# MotorDriver.net
KiCad netlist of a schematic drawn in Altium Designer
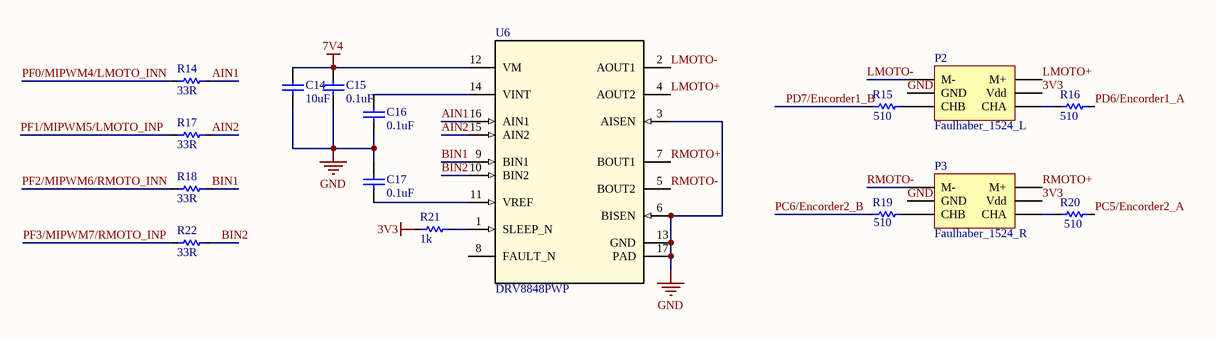
[diagram p0: MotorDriver.SchDoc]

(export (version "E")
  (design (tool "Eeschema 10.0.6"))
  (components
    (comp (ref "C14")
      (value "10uF")
      (footprint "1206")
      (description "Capacitor")
      (fields (field (name "Comment") "1uF/0603/50V") (field (name "PUBLISHER") "Altium Limited"))
      (libsource (lib "OurSuperMiniCar") (part "Cap"))
    )
    (comp (ref "C15")
      (value "0.1uF")
      (footprint "0603C")
      (description "Capacitor")
      (fields (field (name "Comment") "1uF/0603/50V") (field (name "PUBLISHER") "Altium Limited"))
      (libsource (lib "OurSuperMiniCar") (part "Cap"))
    )
    (comp (ref "C16")
      (value "0.1uF")
      (footprint "0603C")
      (description "Capacitor")
      (fields (field (name "Comment") "1uF/0603/50V") (field (name "PUBLISHER") "Altium Limited"))
      (libsource (lib "OurSuperMiniCar") (part "Cap"))
    )
    (comp (ref "C17")
      (value "0.1uF")
      (footprint "0603C")
      (description "Capacitor")
      (fields (field (name "Comment") "1uF/0603/50V") (field (name "PUBLISHER") "Altium Limited"))
      (libsource (lib "OurSuperMiniCar") (part "Cap"))
    )
    (comp (ref "P2")
      (value "Faulhaber_1524_L")
      (footprint "HDR2X3_2.0Mm")
      (libsource (lib "OurSuperMiniCar") (part "Faulhaber_1524"))
    )
    (comp (ref "P3")
      (value "Faulhaber_1524_R")
      (footprint "HDR2X3_2.0Mm")
      (libsource (lib "OurSuperMiniCar") (part "Faulhaber_1524"))
    )
    (comp (ref "R14")
      (value "33R")
      (footprint "0603R")
      (description "Resistor")
      (fields (field (name "PUBLISHER") "Altium Limited"))
      (libsource (lib "OurSuperMiniCar") (part "Res1"))
    )
    (comp (ref "R15")
      (value "510")
      (footprint "0603R")
      (description "Resistor")
      (fields (field (name "Comment") "1K/5%") (field (name "PUBLISHER") "Altium Limited"))
      (libsource (lib "MyComoonents") (part "Res1"))
    )
    (comp (ref "R16")
      (value "510")
      (footprint "0603R")
      (description "Resistor")
      (fields (field (name "PUBLISHER") "Altium Limited"))
      (libsource (lib "MyComoonents") (part "Res1"))
    )
    (comp (ref "R17")
      (value "33R")
      (footprint "0603R")
      (description "Resistor")
      (fields (field (name "PUBLISHER") "Altium Limited"))
      (libsource (lib "OurSuperMiniCar") (part "Res1"))
    )
    (comp (ref "R18")
      (value "33R")
      (footprint "0603R")
      (description "Resistor")
      (fields (field (name "PUBLISHER") "Altium Limited"))
      (libsource (lib "OurSuperMiniCar") (part "Res1"))
    )
    (comp (ref "R19")
      (value "510")
      (footprint "0603R")
      (description "Resistor")
      (fields (field (name "Comment") "1K/5%") (field (name "PUBLISHER") "Altium Limited"))
      (libsource (lib "MyComoonents") (part "Res1"))
    )
    (comp (ref "R20")
      (value "510")
      (footprint "0603R")
      (description "Resistor")
      (fields (field (name "Comment") "1K/5%") (field (name "PUBLISHER") "Altium Limited"))
      (libsource (lib "MyComoonents") (part "Res1"))
    )
    (comp (ref "R21")
      (value "1k")
      (footprint "0603R")
      (description "Resistor")
      (fields (field (name "PUBLISHER") "Altium Limited"))
      (libsource (lib "OurSuperMiniCar") (part "Res1"))
    )
    (comp (ref "R22")
      (value "33R")
      (footprint "0603R")
      (description "Resistor")
      (fields (field (name "PUBLISHER") "Altium Limited"))
      (libsource (lib "OurSuperMiniCar") (part "Res1"))
    )
    (comp (ref "U6")
      (value "DRV8848PWP")
      (footprint "HSSOP_N")
      (description "Imported")
      (fields (field (name "PARTNUMBER") "DRV8848PWPR") (field (name "MANUFACTURER") "Texas Instruments"))
      (libsource (lib "OurSuperMiniCar") (part "DRV8848PWP"))
    )
  )
  (nets
    (net (code "1") (name "/AIN1") (class "Default")
      (node (ref "R14") (pin "2") (pinfunction "2_2") (pintype "passive"))
      (node (ref "U6") (pin "16") (pinfunction "AIN1_16") (pintype "input"))
    )
    (net (code "2") (name "/AIN2") (class "Default")
      (node (ref "R17") (pin "2") (pinfunction "2_2") (pintype "passive"))
      (node (ref "U6") (pin "15") (pinfunction "AIN2_15") (pintype "input"))
    )
    (net (code "3") (name "/BIN1") (class "Default")
      (node (ref "R18") (pin "2") (pinfunction "2_2") (pintype "passive"))
      (node (ref "U6") (pin "9") (pinfunction "BIN1_9") (pintype "input"))
    )
    (net (code "4") (name "/BIN2") (class "Default")
      (node (ref "R22") (pin "2") (pinfunction "2_2") (pintype "passive"))
      (node (ref "U6") (pin "10") (pinfunction "BIN2_10") (pintype "input"))
    )
    (net (code "5") (name "/LMOTO+") (class "Default")
      (node (ref "P2") (pin "2") (pinfunction "M+_2") (pintype "passive"))
      (node (ref "U6") (pin "4") (pinfunction "AOUT2_4") (pintype "power_in"))
    )
    (net (code "6") (name "/LMOTO-") (class "Default")
      (node (ref "P2") (pin "1") (pinfunction "M-_1") (pintype "passive"))
      (node (ref "U6") (pin "2") (pinfunction "AOUT1_2") (pintype "power_in"))
    )
    (net (code "7") (name "/PC5{slash}Encorder2_A") (class "Default")
      (node (ref "R20") (pin "2") (pinfunction "2_2") (pintype "passive"))
    )
    (net (code "8") (name "/PC6{slash}Encorder2_B") (class "Default")
      (node (ref "R19") (pin "1") (pinfunction "1_1") (pintype "passive"))
    )
    (net (code "9") (name "/PD6{slash}Encorder1_A") (class "Default")
      (node (ref "R16") (pin "2") (pinfunction "2_2") (pintype "passive"))
    )
    (net (code "10") (name "/PD7{slash}Encorder1_B") (class "Default")
      (node (ref "R15") (pin "1") (pinfunction "1_1") (pintype "passive"))
    )
    (net (code "11") (name "/PF0{slash}MIPWM4{slash}LMOTO_INN") (class "Default")
      (node (ref "R14") (pin "1") (pinfunction "1_1") (pintype "passive"))
    )
    (net (code "12") (name "/PF1{slash}MIPWM5{slash}LMOTO_INP") (class "Default")
      (node (ref "R17") (pin "1") (pinfunction "1_1") (pintype "passive"))
    )
    (net (code "13") (name "/PF2{slash}MIPWM6{slash}RMOTO_INN") (class "Default")
      (node (ref "R18") (pin "1") (pinfunction "1_1") (pintype "passive"))
    )
    (net (code "14") (name "/PF3{slash}MIPWM7{slash}RMOTO_INP") (class "Default")
      (node (ref "R22") (pin "1") (pinfunction "1_1") (pintype "passive"))
    )
    (net (code "15") (name "/RMOTO+") (class "Default")
      (node (ref "P3") (pin "2") (pinfunction "M+_2") (pintype "passive"))
      (node (ref "U6") (pin "7") (pinfunction "BOUT1_7") (pintype "power_in"))
    )
    (net (code "16") (name "/RMOTO-") (class "Default")
      (node (ref "P3") (pin "1") (pinfunction "M-_1") (pintype "passive"))
      (node (ref "U6") (pin "5") (pinfunction "BOUT2_5") (pintype "power_in"))
    )
    (net (code "17") (name "3V3") (class "Default")
      (node (ref "P2") (pin "4") (pinfunction "Vdd_4") (pintype "passive"))
      (node (ref "P3") (pin "4") (pinfunction "Vdd_4") (pintype "passive"))
      (node (ref "R21") (pin "1") (pinfunction "1_1") (pintype "passive"))
    )
    (net (code "18") (name "7V4") (class "Default")
      (node (ref "C14") (pin "1") (pinfunction "1_1") (pintype "passive"))
      (node (ref "C15") (pin "1") (pinfunction "1_1") (pintype "passive"))
      (node (ref "U6") (pin "12") (pinfunction "VM_12") (pintype "power_in"))
    )
    (net (code "19") (name "GND") (class "Default")
      (node (ref "C14") (pin "2") (pinfunction "2_2") (pintype "passive"))
      (node (ref "C15") (pin "2") (pinfunction "2_2") (pintype "passive"))
      (node (ref "C16") (pin "2") (pinfunction "2_2") (pintype "passive"))
      (node (ref "C17") (pin "2") (pinfunction "2_2") (pintype "passive"))
      (node (ref "P2") (pin "3") (pinfunction "GND_3") (pintype "passive"))
      (node (ref "P3") (pin "3") (pinfunction "GND_3") (pintype "passive"))
      (node (ref "U6") (pin "13") (pinfunction "GND_13") (pintype "power_in"))
      (node (ref "U6") (pin "17") (pinfunction "PAD_17") (pintype "power_in"))
      (node (ref "U6") (pin "3") (pinfunction "AISEN_3") (pintype "input"))
      (node (ref "U6") (pin "6") (pinfunction "BISEN_6") (pintype "input"))
    )
    (net (code "20") (name "Net-(P2-CHA)") (class "Default")
      (node (ref "P2") (pin "6") (pinfunction "CHA_6") (pintype "passive"))
      (node (ref "R16") (pin "1") (pinfunction "1_1") (pintype "passive"))
    )
    (net (code "21") (name "Net-(P2-CHB)") (class "Default")
      (node (ref "P2") (pin "5") (pinfunction "CHB_5") (pintype "passive"))
      (node (ref "R15") (pin "2") (pinfunction "2_2") (pintype "passive"))
    )
    (net (code "22") (name "Net-(P3-CHA)") (class "Default")
      (node (ref "P3") (pin "6") (pinfunction "CHA_6") (pintype "passive"))
      (node (ref "R20") (pin "1") (pinfunction "1_1") (pintype "passive"))
    )
    (net (code "23") (name "Net-(P3-CHB)") (class "Default")
      (node (ref "P3") (pin "5") (pinfunction "CHB_5") (pintype "passive"))
      (node (ref "R19") (pin "2") (pinfunction "2_2") (pintype "passive"))
    )
    (net (code "24") (name "Net-(U6-SLEEP_N)") (class "Default")
      (node (ref "R21") (pin "2") (pinfunction "2_2") (pintype "passive"))
      (node (ref "U6") (pin "1") (pinfunction "SLEEP_N_1") (pintype "input"))
    )
    (net (code "25") (name "Net-(U6-VINT)") (class "Default")
      (node (ref "C16") (pin "1") (pinfunction "1_1") (pintype "passive"))
      (node (ref "U6") (pin "14") (pinfunction "VINT_14") (pintype "power_in"))
    )
    (net (code "26") (name "Net-(U6-VREF)") (class "Default")
      (node (ref "C17") (pin "1") (pinfunction "1_1") (pintype "passive"))
      (node (ref "U6") (pin "11") (pinfunction "VREF_11") (pintype "input"))
    )
    (net (code "27") (name "unconnected-(U6-FAULT_N-Pad8)") (class "Default")
      (node (ref "U6") (pin "8") (pinfunction "FAULT_N_8") (pintype "open_collector"))
    )
  )
)
